# 3_esc_power_sw.net
KiCad netlist of a schematic drawn in Altium Designer
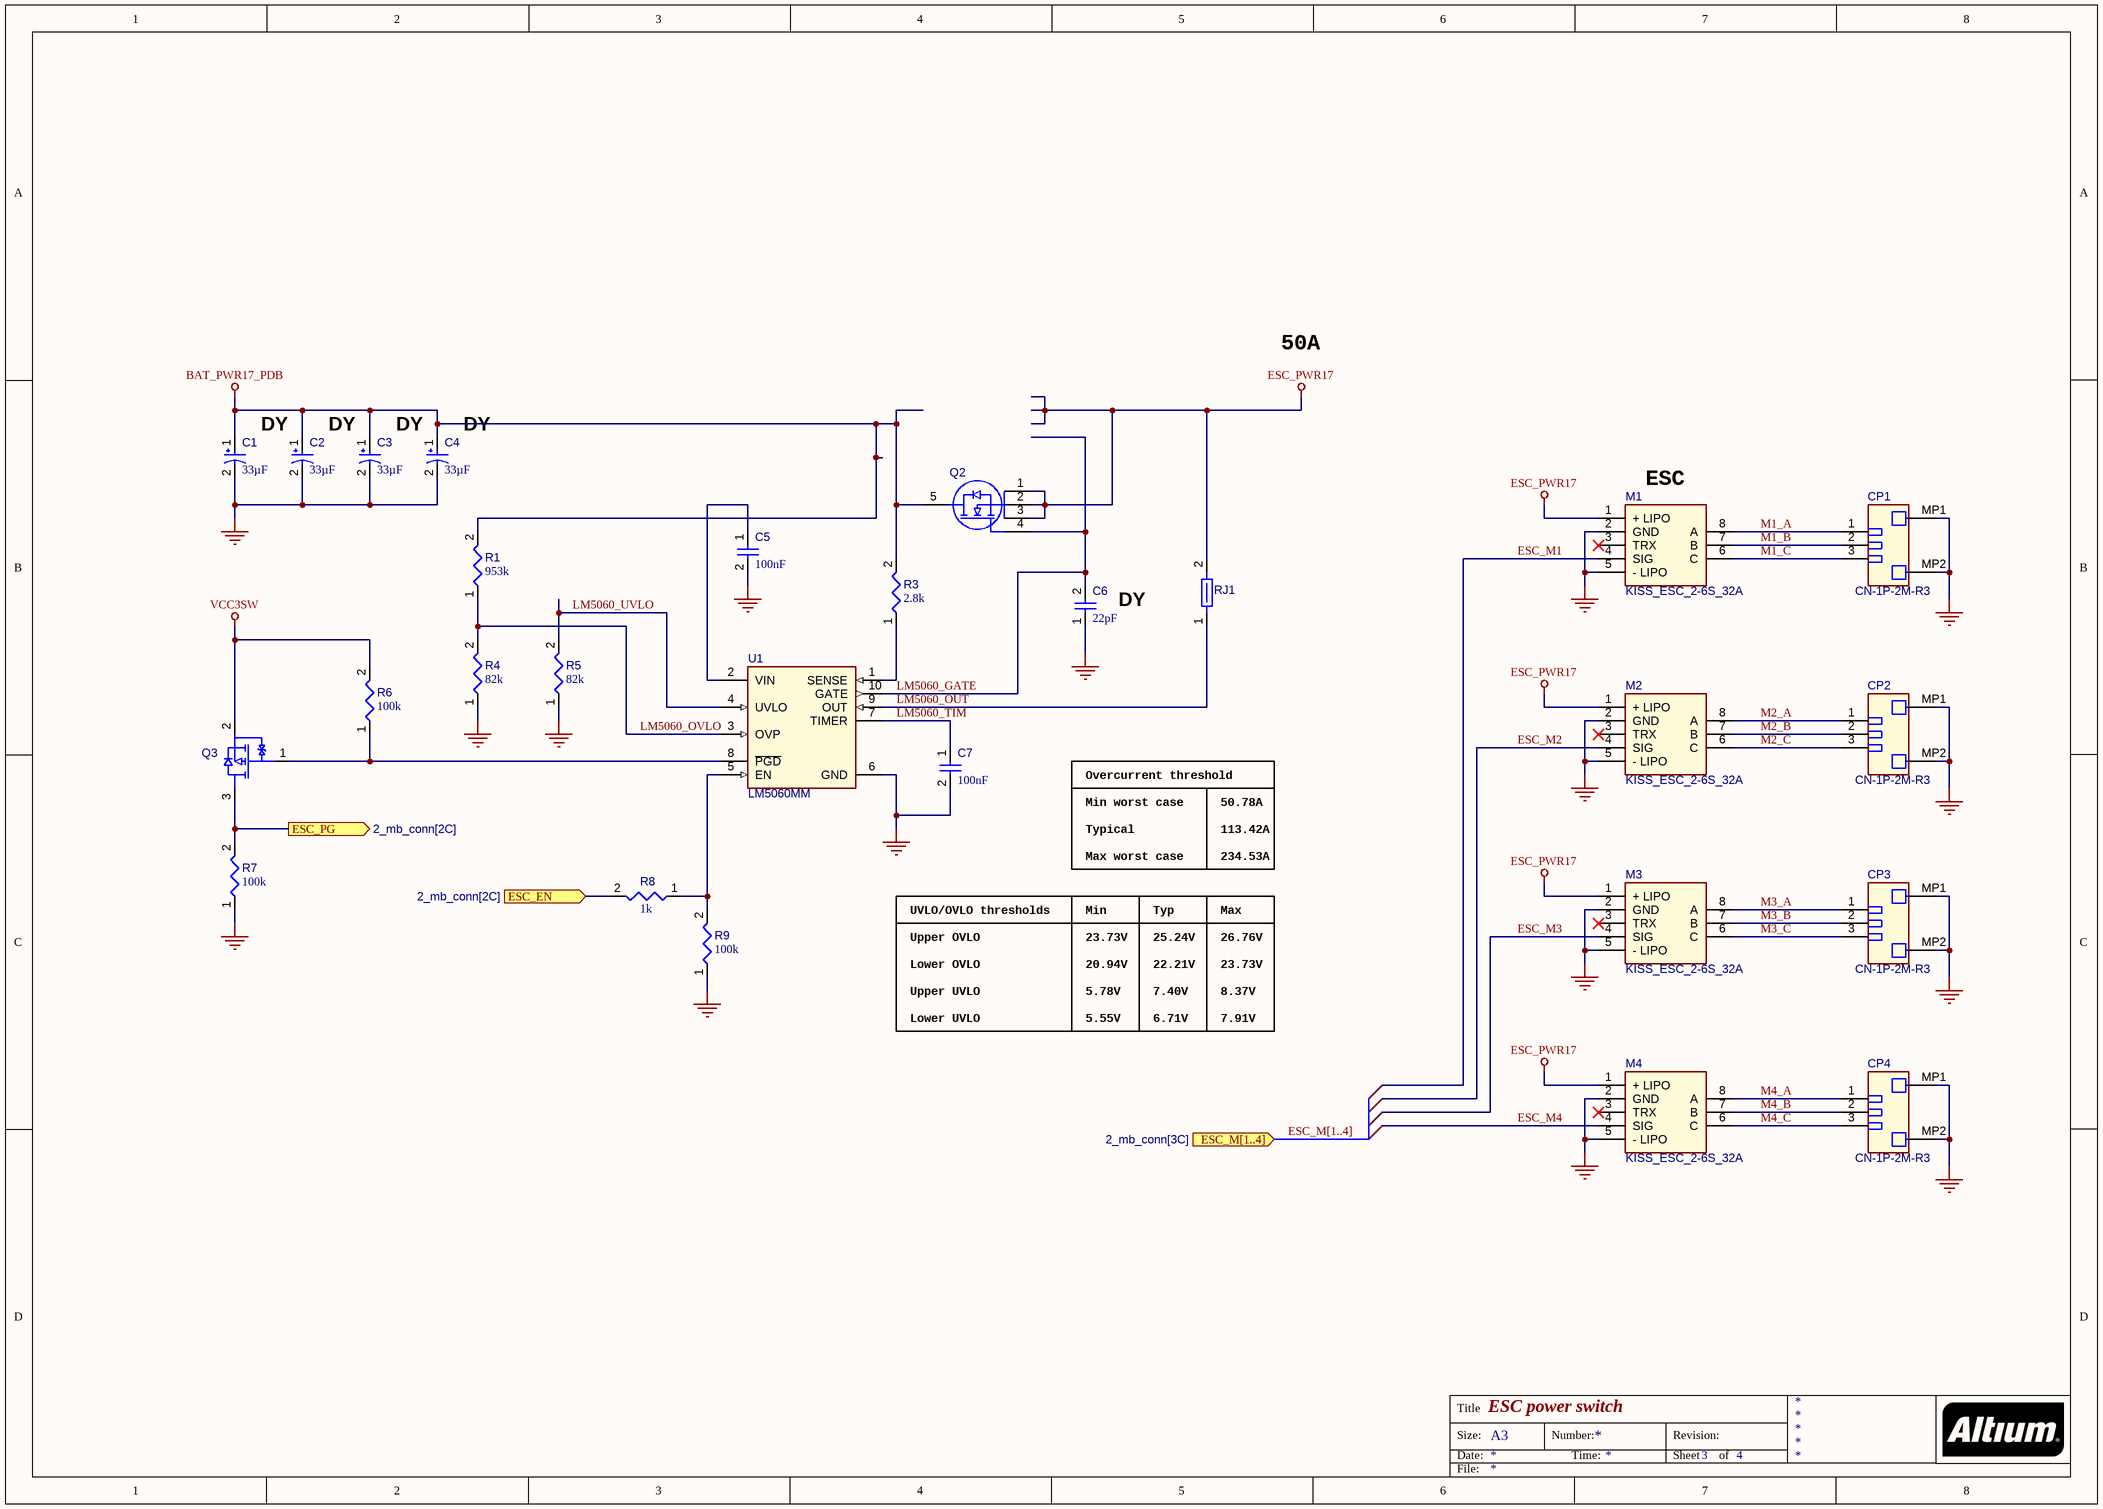
[diagram p0: 3_esc_power_sw.SchDoc]

(export (version "E")
  (design (tool "Eeschema 10.0.6"))
  (components
    (comp (ref "C1")
      (value "33µF")
      (footprint "EEF-CX1E330R-Footprint-1")
      (description "Aluminum Organic Polymer Capacitors 33uF 25volt SP-Cap AEC-Q200")
      (fields (field (name "TOLERANCE") "20%") (field (name "Comment") "Capacitor 33µF +/-20% 25V 2917"))
      (libsource (lib "<Company> Server") (part "CAP-P-2"))
    )
    (comp (ref "C2")
      (value "33µF")
      (footprint "EEF-CX1E330R-Footprint-1")
      (description "Aluminum Organic Polymer Capacitors 33uF 25volt SP-Cap AEC-Q200")
      (fields (field (name "TOLERANCE") "20%") (field (name "Comment") "Capacitor 33µF +/-20% 25V 2917"))
      (libsource (lib "<Company> Server") (part "CAP-P-2"))
    )
    (comp (ref "C3")
      (value "33µF")
      (footprint "EEF-CX1E330R-Footprint-1")
      (description "Aluminum Organic Polymer Capacitors 33uF 25volt SP-Cap AEC-Q200")
      (fields (field (name "TOLERANCE") "20%") (field (name "Comment") "Capacitor 33µF +/-20% 25V 2917"))
      (libsource (lib "<Company> Server") (part "CAP-P-2"))
    )
    (comp (ref "C4")
      (value "33µF")
      (footprint "EEF-CX1E330R-Footprint-1")
      (description "Aluminum Organic Polymer Capacitors 33uF 25volt SP-Cap AEC-Q200")
      (fields (field (name "TOLERANCE") "20%") (field (name "Comment") "Capacitor 33µF +/-20% 25V 2917"))
      (libsource (lib "<Company> Server") (part "CAP-P-2"))
    )
    (comp (ref "C5")
      (value "100nF")
      (footprint "CAPC0402(1005)60_L")
      (description "Chip Capacitor, 100nF +/-20%, 50V, 0402, Thickness 0.6 mm")
      (fields (field (name "TOLERANCE") "10%") (field (name "Comment") "Capacitor 100nF +/-20% 50V 0402"))
      (libsource (lib "<Company> Server") (part "CAP-NP-2"))
    )
    (comp (ref "C6")
      (value "22pF")
      (footprint "CAPC0402(1005)60_L")
      (description "Chip Capacitor, 22pF +/-10%, 50V, 0402, Thickness 0.6 mm")
      (fields (field (name "TOLERANCE") "10%") (field (name "Comment") "Capacitor 22pF +/-10% 50V 0402"))
      (libsource (lib "<Company> Server") (part "CAP-NP-2"))
    )
    (comp (ref "C7")
      (value "100nF")
      (footprint "CAPC0402(1005)60_L")
      (description "Chip Capacitor, 100nF +/-20%, 50V, 0402, Thickness 0.6 mm")
      (fields (field (name "TOLERANCE") "10%") (field (name "Comment") "Capacitor 100nF +/-20% 50V 0402"))
      (libsource (lib "<Company> Server") (part "CAP-NP-2"))
    )
    (comp (ref "CP1")
      (value "CN-1P-2M-R3")
      (footprint "MR30PW-FB-Footprint-1")
      (description "AMASS 500V 15A   0.8 mOhm")
      (libsource (lib "<Company> Server") (part "CMP-001-0016-5"))
    )
    (comp (ref "CP2")
      (value "CN-1P-2M-R3")
      (footprint "MR30PW-FB-Footprint-1")
      (description "AMASS 500V 15A   0.8 mOhm")
      (libsource (lib "<Company> Server") (part "CMP-001-0016-5"))
    )
    (comp (ref "CP3")
      (value "CN-1P-2M-R3")
      (footprint "MR30PW-FB-Footprint-1")
      (description "AMASS 500V 15A   0.8 mOhm")
      (libsource (lib "<Company> Server") (part "CMP-001-0016-5"))
    )
    (comp (ref "CP4")
      (value "CN-1P-2M-R3")
      (footprint "MR30PW-FB-Footprint-1")
      (description "AMASS 500V 15A   0.8 mOhm")
      (libsource (lib "<Company> Server") (part "CMP-001-0016-5"))
    )
    (comp (ref "M1")
      (value "KISS_ESC_2-6S_32A")
      (footprint "ESC 2-6S 32A-Footprint-1")
      (description "KISS ESC 2-6S 32A (45A limit) - 32bit brushless Motor Ctrl")
      (libsource (lib "<Company> Server") (part "CMP-001-0017-10"))
    )
    (comp (ref "M2")
      (value "KISS_ESC_2-6S_32A")
      (footprint "ESC 2-6S 32A-Footprint-1")
      (description "KISS ESC 2-6S 32A (45A limit) - 32bit brushless Motor Ctrl")
      (libsource (lib "<Company> Server") (part "CMP-001-0017-10"))
    )
    (comp (ref "M3")
      (value "KISS_ESC_2-6S_32A")
      (footprint "ESC 2-6S 32A-Footprint-1")
      (description "KISS ESC 2-6S 32A (45A limit) - 32bit brushless Motor Ctrl")
      (libsource (lib "<Company> Server") (part "CMP-001-0017-10"))
    )
    (comp (ref "M4")
      (value "KISS_ESC_2-6S_32A")
      (footprint "ESC 2-6S 32A-Footprint-1")
      (description "KISS ESC 2-6S 32A (45A limit) - 32bit brushless Motor Ctrl")
      (libsource (lib "<Company> Server") (part "CMP-001-0017-10"))
    )
    (comp (ref "Q2")
      (value "PSMN1R0-30YLDX")
      (footprint "NXP-SOT669_L")
      (description "N-channel Logic Level MOSFET, 30 V, 300 A, -55 to 175 degC, 5-Pin SOT669, RoHS, Tape and Reel")
      (libsource (lib "<Company> Server") (part "CMP-00089-6"))
    )
    (comp (ref "Q3")
      (value "RZM002P02T2L")
      (footprint "ROHM-SOT723-3_V")
      (description "Pch Small Signal MOSFET, 20 V, 200 mA, 3-Pin SOT723, RoHS, Tape and Reel")
      (libsource (lib "<Company> Server") (part "CMP-00006-6"))
    )
    (comp (ref "R1")
      (value "953k")
      (footprint "RESC0402(1005)_L")
      (description "Chip Resistor, 953 kOhms, +/-1 %, 63 mW, -55 to 155 degC, 0402")
      (fields (field (name "POWER") "63mW") (field (name "TOLERANCE") "1%"))
      (libsource (lib "<Company> Server") (part "RES-2"))
    )
    (comp (ref "R3")
      (value "2.8k")
      (footprint "RESC0402(1005)_L")
      (description "Chip Resistor, 2,8 kOhms, +/-1 %, 63 mW, -55 to 155 degC, 0402")
      (fields (field (name "POWER") "63mW") (field (name "TOLERANCE") "1%"))
      (libsource (lib "<Company> Server") (part "RES-2"))
    )
    (comp (ref "R4")
      (value "82k")
      (footprint "RESC0402(1005)_L")
      (description "Chip Resistor, 82 kOhms, +/-1 %, 63 mW, -55 to 155 degC, 0402")
      (fields (field (name "TOLERANCE") "1%") (field (name "POWER") "63mW"))
      (libsource (lib "<Company> Server") (part "RES-2"))
    )
    (comp (ref "R5")
      (value "82k")
      (footprint "RESC0402(1005)_L")
      (description "Chip Resistor, 82 kOhms, +/-1 %, 63 mW, -55 to 155 degC, 0402")
      (fields (field (name "TOLERANCE") "1%") (field (name "POWER") "63mW"))
      (libsource (lib "<Company> Server") (part "RES-2"))
    )
    (comp (ref "R6")
      (value "100k")
      (footprint "RESC0402(1005)_L")
      (description "Chip Resistor, 100 kOhms, +/-1 %, 63 mW, -55 to 155 degC, 0402")
      (fields (field (name "TOLERANCE") "1%") (field (name "POWER") "63mW"))
      (libsource (lib "<Company> Server") (part "RES-2"))
    )
    (comp (ref "R7")
      (value "100k")
      (footprint "RESC0402(1005)_L")
      (description "Chip Resistor, 100 kOhms, +/-1 %, 63 mW, -55 to 155 degC, 0402")
      (fields (field (name "TOLERANCE") "1%") (field (name "POWER") "63mW"))
      (libsource (lib "<Company> Server") (part "RES-2"))
    )
    (comp (ref "R8")
      (value "1k")
      (footprint "RESC0402(1005)_L")
      (description "Chip Resistor, 1 kOhms, +/-5 %, 63 mW, -55 to 155 degC, 0402")
      (fields (field (name "TOLERANCE") "5%") (field (name "POWER") "63mW"))
      (libsource (lib "<Company> Server") (part "RES-2"))
    )
    (comp (ref "R9")
      (value "100k")
      (footprint "RESC0402(1005)_L")
      (description "Chip Resistor, 100 kOhms, +/-1 %, 63 mW, -55 to 155 degC, 0402")
      (fields (field (name "TOLERANCE") "1%") (field (name "POWER") "63mW"))
      (libsource (lib "<Company> Server") (part "RES-2"))
    )
    (comp (ref "RJ1")
      (value "Net Tie 10x8mil")
      (footprint "New footprint 1")
      (libsource (lib "<Company> Server") (part "CMP-00022-00002-2"))
    )
    (comp (ref "U1")
      (value "LM5060MM")
      (footprint "DGS0010A_N")
      (libsource (lib "<Company> Server") (part "CMP-00082-3"))
    )
  )
  (nets
    (net (code "1") (name "/ESC_EN") (class "Default")
      (node (ref "R8") (pin "2") (pinfunction "2_2") (pintype "passive"))
    )
    (net (code "2") (name "/ESC_M1") (class "Default")
      (node (ref "M1") (pin "4") (pinfunction "SIG_4") (pintype "passive"))
    )
    (net (code "3") (name "/ESC_M2") (class "Default")
      (node (ref "M2") (pin "4") (pinfunction "SIG_4") (pintype "passive"))
    )
    (net (code "4") (name "/ESC_M3") (class "Default")
      (node (ref "M3") (pin "4") (pinfunction "SIG_4") (pintype "passive"))
    )
    (net (code "5") (name "/ESC_M4") (class "Default")
      (node (ref "M4") (pin "4") (pinfunction "SIG_4") (pintype "passive"))
    )
    (net (code "7") (name "/ESC_PG") (class "Default")
      (node (ref "Q3") (pin "3") (pinfunction "D_3") (pintype "passive"))
      (node (ref "R7") (pin "2") (pinfunction "2_2") (pintype "passive"))
    )
    (net (code "8") (name "/LM5060_GATE") (class "Default")
      (node (ref "C6") (pin "2") (pinfunction "2_2") (pintype "passive"))
      (node (ref "Q2") (pin "4") (pinfunction "G_4") (pintype "passive"))
      (node (ref "U1") (pin "10") (pinfunction "GATE_10") (pintype "output"))
    )
    (net (code "9") (name "/LM5060_OUT") (class "Default")
      (node (ref "RJ1") (pin "1") (pinfunction "1_1") (pintype "passive"))
      (node (ref "U1") (pin "9") (pinfunction "OUT_9") (pintype "input"))
    )
    (net (code "10") (name "/LM5060_OVLO") (class "Default")
      (node (ref "R1") (pin "1") (pinfunction "1_1") (pintype "passive"))
      (node (ref "R4") (pin "2") (pinfunction "2_2") (pintype "passive"))
      (node (ref "U1") (pin "3") (pinfunction "OVP_3") (pintype "input"))
    )
    (net (code "11") (name "/LM5060_TIM") (class "Default")
      (node (ref "C7") (pin "1") (pinfunction "1_1") (pintype "passive"))
      (node (ref "U1") (pin "7") (pinfunction "TIMER_7") (pintype "passive"))
    )
    (net (code "12") (name "/LM5060_UVLO") (class "Default")
      (node (ref "R5") (pin "2") (pinfunction "2_2") (pintype "passive"))
      (node (ref "U1") (pin "4") (pinfunction "UVLO_4") (pintype "input"))
    )
    (net (code "13") (name "/M1_A") (class "Default")
      (node (ref "CP1") (pin "1") (pinfunction "1_1") (pintype "passive"))
      (node (ref "M1") (pin "8") (pinfunction "A_8") (pintype "passive"))
    )
    (net (code "14") (name "/M1_B") (class "Default")
      (node (ref "CP1") (pin "2") (pinfunction "2_2") (pintype "passive"))
      (node (ref "M1") (pin "7") (pinfunction "B_7") (pintype "passive"))
    )
    (net (code "15") (name "/M1_C") (class "Default")
      (node (ref "CP1") (pin "3") (pinfunction "3_3") (pintype "passive"))
      (node (ref "M1") (pin "6") (pinfunction "C_6") (pintype "passive"))
    )
    (net (code "16") (name "/M2_A") (class "Default")
      (node (ref "CP2") (pin "1") (pinfunction "1_1") (pintype "passive"))
      (node (ref "M2") (pin "8") (pinfunction "A_8") (pintype "passive"))
    )
    (net (code "17") (name "/M2_B") (class "Default")
      (node (ref "CP2") (pin "2") (pinfunction "2_2") (pintype "passive"))
      (node (ref "M2") (pin "7") (pinfunction "B_7") (pintype "passive"))
    )
    (net (code "18") (name "/M2_C") (class "Default")
      (node (ref "CP2") (pin "3") (pinfunction "3_3") (pintype "passive"))
      (node (ref "M2") (pin "6") (pinfunction "C_6") (pintype "passive"))
    )
    (net (code "19") (name "/M3_A") (class "Default")
      (node (ref "CP3") (pin "1") (pinfunction "1_1") (pintype "passive"))
      (node (ref "M3") (pin "8") (pinfunction "A_8") (pintype "passive"))
    )
    (net (code "20") (name "/M3_B") (class "Default")
      (node (ref "CP3") (pin "2") (pinfunction "2_2") (pintype "passive"))
      (node (ref "M3") (pin "7") (pinfunction "B_7") (pintype "passive"))
    )
    (net (code "21") (name "/M3_C") (class "Default")
      (node (ref "CP3") (pin "3") (pinfunction "3_3") (pintype "passive"))
      (node (ref "M3") (pin "6") (pinfunction "C_6") (pintype "passive"))
    )
    (net (code "22") (name "/M4_A") (class "Default")
      (node (ref "CP4") (pin "1") (pinfunction "1_1") (pintype "passive"))
      (node (ref "M4") (pin "8") (pinfunction "A_8") (pintype "passive"))
    )
    (net (code "23") (name "/M4_B") (class "Default")
      (node (ref "CP4") (pin "2") (pinfunction "2_2") (pintype "passive"))
      (node (ref "M4") (pin "7") (pinfunction "B_7") (pintype "passive"))
    )
    (net (code "24") (name "/M4_C") (class "Default")
      (node (ref "CP4") (pin "3") (pinfunction "3_3") (pintype "passive"))
      (node (ref "M4") (pin "6") (pinfunction "C_6") (pintype "passive"))
    )
    (net (code "25") (name "BAT_PWR17_PDB") (class "Default")
      (node (ref "C1") (pin "1") (pinfunction "1_1") (pintype "passive"))
      (node (ref "C2") (pin "1") (pinfunction "1_1") (pintype "passive"))
      (node (ref "C3") (pin "1") (pinfunction "1_1") (pintype "passive"))
      (node (ref "C4") (pin "1") (pinfunction "1_1") (pintype "passive"))
      (node (ref "Q2") (pin "5") (pinfunction "D_5") (pintype "passive"))
      (node (ref "R1") (pin "2") (pinfunction "2_2") (pintype "passive"))
      (node (ref "R3") (pin "2") (pinfunction "2_2") (pintype "passive"))
    )
    (net (code "26") (name "ESC_PWR17") (class "Default")
      (node (ref "M1") (pin "1") (pinfunction "+_LIPO_1") (pintype "passive"))
      (node (ref "M2") (pin "1") (pinfunction "+_LIPO_1") (pintype "passive"))
      (node (ref "M3") (pin "1") (pinfunction "+_LIPO_1") (pintype "passive"))
      (node (ref "M4") (pin "1") (pinfunction "+_LIPO_1") (pintype "passive"))
      (node (ref "Q2") (pin "1") (pinfunction "S_1") (pintype "passive"))
      (node (ref "Q2") (pin "2") (pinfunction "S_2") (pintype "passive"))
      (node (ref "Q2") (pin "3") (pinfunction "S_3") (pintype "passive"))
      (node (ref "RJ1") (pin "2") (pinfunction "2_2") (pintype "passive"))
    )
    (net (code "27") (name "GND") (class "Default")
      (node (ref "C1") (pin "2") (pinfunction "2_2") (pintype "passive"))
      (node (ref "C2") (pin "2") (pinfunction "2_2") (pintype "passive"))
      (node (ref "C3") (pin "2") (pinfunction "2_2") (pintype "passive"))
      (node (ref "C4") (pin "2") (pinfunction "2_2") (pintype "passive"))
      (node (ref "C5") (pin "2") (pinfunction "2_2") (pintype "passive"))
      (node (ref "C6") (pin "1") (pinfunction "1_1") (pintype "passive"))
      (node (ref "C7") (pin "2") (pinfunction "2_2") (pintype "passive"))
      (node (ref "CP1") (pin "MP1") (pinfunction "MP1_MP1") (pintype "passive"))
      (node (ref "CP1") (pin "MP2") (pinfunction "MP2_MP2") (pintype "passive"))
      (node (ref "CP2") (pin "MP1") (pinfunction "MP1_MP1") (pintype "passive"))
      (node (ref "CP2") (pin "MP2") (pinfunction "MP2_MP2") (pintype "passive"))
      (node (ref "CP3") (pin "MP1") (pinfunction "MP1_MP1") (pintype "passive"))
      (node (ref "CP3") (pin "MP2") (pinfunction "MP2_MP2") (pintype "passive"))
      (node (ref "CP4") (pin "MP1") (pinfunction "MP1_MP1") (pintype "passive"))
      (node (ref "CP4") (pin "MP2") (pinfunction "MP2_MP2") (pintype "passive"))
      (node (ref "M1") (pin "2") (pinfunction "GND_2") (pintype "passive"))
      (node (ref "M1") (pin "5") (pinfunction "-_LIPO_5") (pintype "passive"))
      (node (ref "M2") (pin "2") (pinfunction "GND_2") (pintype "passive"))
      (node (ref "M2") (pin "5") (pinfunction "-_LIPO_5") (pintype "passive"))
      (node (ref "M3") (pin "2") (pinfunction "GND_2") (pintype "passive"))
      (node (ref "M3") (pin "5") (pinfunction "-_LIPO_5") (pintype "passive"))
      (node (ref "M4") (pin "2") (pinfunction "GND_2") (pintype "passive"))
      (node (ref "M4") (pin "5") (pinfunction "-_LIPO_5") (pintype "passive"))
      (node (ref "R4") (pin "1") (pinfunction "1_1") (pintype "passive"))
      (node (ref "R5") (pin "1") (pinfunction "1_1") (pintype "passive"))
      (node (ref "R7") (pin "1") (pinfunction "1_1") (pintype "passive"))
      (node (ref "R9") (pin "1") (pinfunction "1_1") (pintype "passive"))
      (node (ref "U1") (pin "6") (pinfunction "GND_6") (pintype "power_in"))
    )
    (net (code "28") (name "Net-(Q3-G)") (class "Default")
      (node (ref "Q3") (pin "1") (pinfunction "G_1") (pintype "passive"))
      (node (ref "R6") (pin "1") (pinfunction "1_1") (pintype "passive"))
      (node (ref "U1") (pin "8") (pinfunction "~{PGD}_8") (pintype "open_collector"))
    )
    (net (code "29") (name "Net-(U1-EN)") (class "Default")
      (node (ref "R8") (pin "1") (pinfunction "1_1") (pintype "passive"))
      (node (ref "R9") (pin "2") (pinfunction "2_2") (pintype "passive"))
      (node (ref "U1") (pin "5") (pinfunction "EN_5") (pintype "input"))
    )
    (net (code "30") (name "Net-(U1-SENSE)") (class "Default")
      (node (ref "R3") (pin "1") (pinfunction "1_1") (pintype "passive"))
      (node (ref "U1") (pin "1") (pinfunction "SENSE_1") (pintype "input"))
    )
    (net (code "31") (name "Net-(U1-VIN)") (class "Default")
      (node (ref "C5") (pin "1") (pinfunction "1_1") (pintype "passive"))
      (node (ref "U1") (pin "2") (pinfunction "VIN_2") (pintype "power_in"))
    )
    (net (code "32") (name "VCC3SW") (class "Default")
      (node (ref "Q3") (pin "2") (pinfunction "S_2") (pintype "passive"))
      (node (ref "R6") (pin "2") (pinfunction "2_2") (pintype "passive"))
    )
    (net (code "33") (name "unconnected-(M1-TRX-Pad3)") (class "Default")
      (node (ref "M1") (pin "3") (pinfunction "TRX_3") (pintype "passive+no_connect"))
    )
    (net (code "34") (name "unconnected-(M2-TRX-Pad3)") (class "Default")
      (node (ref "M2") (pin "3") (pinfunction "TRX_3") (pintype "passive+no_connect"))
    )
    (net (code "35") (name "unconnected-(M3-TRX-Pad3)") (class "Default")
      (node (ref "M3") (pin "3") (pinfunction "TRX_3") (pintype "passive+no_connect"))
    )
    (net (code "36") (name "unconnected-(M4-TRX-Pad3)") (class "Default")
      (node (ref "M4") (pin "3") (pinfunction "TRX_3") (pintype "passive+no_connect"))
    )
  )
)
